# cpu.net
KiCad netlist of a schematic drawn in Altium Designer
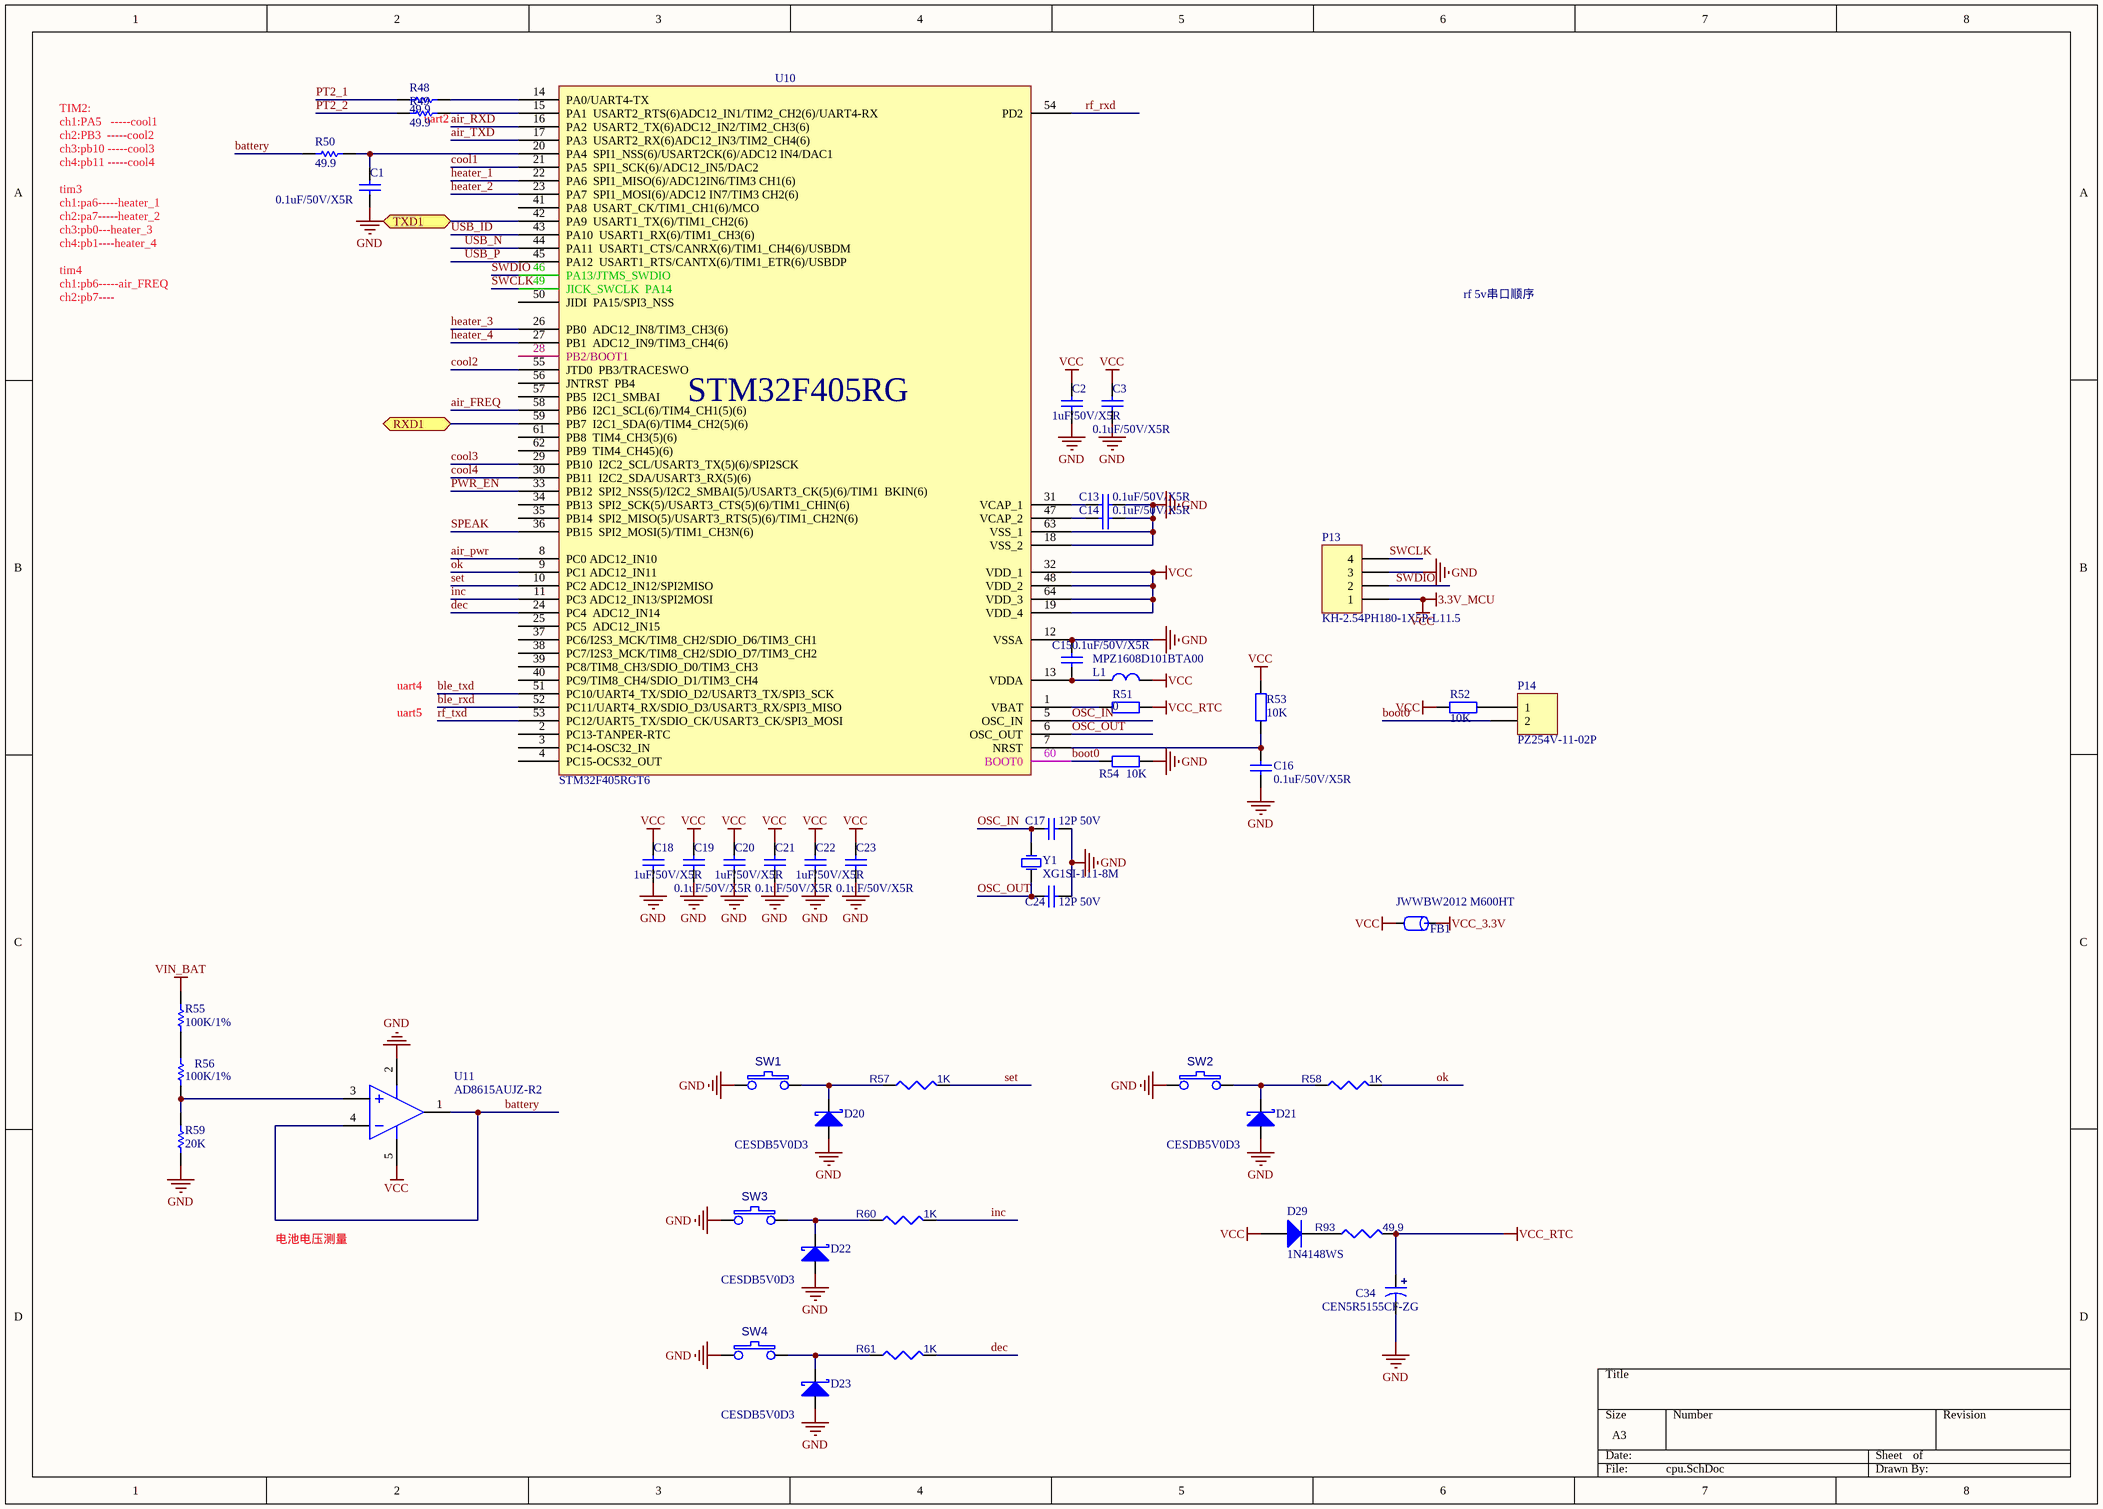
[diagram p0: cpu.SchDoc]

(export (version "E")
  (design (tool "Eeschema 10.0.6"))
  (components
    (comp (ref "C1")
      (value "0.1uF/50V/X5R")
      (footprint "0603C")
      (description "贴片电容 20%")
      (libsource (lib "XiaoyI") (part "CAP4"))
    )
    (comp (ref "C2")
      (value "1uF/50V/X5R")
      (footprint "0603C")
      (description "贴片电容 20%")
      (libsource (lib "XiaoyI") (part "CAP4"))
    )
    (comp (ref "C3")
      (value "0.1uF/50V/X5R")
      (footprint "0603C")
      (description "贴片电容 20%")
      (libsource (lib "XiaoyI") (part "CAP4"))
    )
    (comp (ref "C13")
      (value "0.1uF/50V/X5R")
      (footprint "0603C")
      (description "贴片电容 20%")
      (libsource (lib "XiaoyI") (part "CAP4"))
    )
    (comp (ref "C14")
      (value "0.1uF/50V/X5R")
      (footprint "0603C")
      (description "贴片电容 20%")
      (libsource (lib "XiaoyI") (part "CAP4"))
    )
    (comp (ref "C15")
      (value "0.1uF/50V/X5R")
      (footprint "0603C")
      (description "贴片电容 20%")
      (libsource (lib "XiaoyI") (part "CAP4"))
    )
    (comp (ref "C16")
      (value "0.1uF/50V/X5R")
      (footprint "0603C")
      (description "贴片电容 20%")
      (libsource (lib "XiaoyI") (part "CAP4"))
    )
    (comp (ref "C17")
      (value "12P 50V")
      (footprint "0603C")
      (description "贴片电容 20%")
      (libsource (lib "XiaoyI") (part "CAP4"))
    )
    (comp (ref "C18")
      (value "1uF/50V/X5R")
      (footprint "0603C")
      (description "贴片电容 20%")
      (libsource (lib "XiaoyI") (part "CAP4"))
    )
    (comp (ref "C19")
      (value "0.1uF/50V/X5R")
      (footprint "0603C")
      (description "贴片电容 20%")
      (libsource (lib "XiaoyI") (part "CAP4"))
    )
    (comp (ref "C20")
      (value "1uF/50V/X5R")
      (footprint "0603C")
      (description "贴片电容 20%")
      (libsource (lib "XiaoyI") (part "CAP4"))
    )
    (comp (ref "C21")
      (value "0.1uF/50V/X5R")
      (footprint "0603C")
      (description "贴片电容 20%")
      (libsource (lib "XiaoyI") (part "CAP4"))
    )
    (comp (ref "C22")
      (value "1uF/50V/X5R")
      (footprint "0603C")
      (description "贴片电容 20%")
      (libsource (lib "XiaoyI") (part "CAP4"))
    )
    (comp (ref "C23")
      (value "0.1uF/50V/X5R")
      (footprint "0603C")
      (description "贴片电容 20%")
      (libsource (lib "XiaoyI") (part "CAP4"))
    )
    (comp (ref "C24")
      (value "12P 50V")
      (footprint "0603C")
      (description "贴片电容 20%")
      (libsource (lib "XiaoyI") (part "CAP4"))
    )
    (comp (ref "C34")
      (value "CEN5R5155CF-ZG")
      (footprint "CAP-TH_BD21.0-P5.00-D0.8_CENXXX-CF")
      (description "电解电容")
      (libsource (lib "XiaoyI") (part "CAP2"))
    )
    (comp (ref "D20")
      (value "CESDB5V0D3")
      (footprint "SOD323")
      (description "Schottky Diode")
      (libsource (lib "*") (part "DIODE S"))
    )
    (comp (ref "D21")
      (value "CESDB5V0D3")
      (footprint "SOD323")
      (description "Schottky Diode")
      (libsource (lib "*") (part "DIODE S"))
    )
    (comp (ref "D22")
      (value "CESDB5V0D3")
      (footprint "SOD323")
      (description "Schottky Diode")
      (libsource (lib "*") (part "DIODE S"))
    )
    (comp (ref "D23")
      (value "CESDB5V0D3")
      (footprint "SOD323")
      (description "Schottky Diode")
      (libsource (lib "*") (part "DIODE S"))
    )
    (comp (ref "D29") (value "1N4148WS") (footprint "SOD323") (libsource (lib "Sch_library") (part "DIODE")))
    (comp (ref "FB1")
      (value "JWWBW2012 M600HT")
      (footprint "0805CZ")
      (libsource (lib "Schlib_20110825") (part "FB"))
    )
    (comp (ref "L1")
      (value "MPZ1608D101BTA00")
      (footprint "0603R")
      (description "磁珠电感 100R 100MHz")
      (libsource (lib "XiaoyI") (part "CIZHU1"))
    )
    (comp (ref "P13")
      (value "KH-2.54PH180-1X5P-L11.5")
      (footprint "HDR1X4")
      (description "Header, 4-Pin")
      (fields (field (name "PUBLISHER") "Altium Limited"))
      (libsource (lib "Miscellaneous Connectors") (part "Header 4"))
    )
    (comp (ref "P14")
      (value "PZ254V-11-02P")
      (footprint "HDR1X2")
      (description "Header, 2-Pin")
      (fields (field (name "PUBLISHER") "Altium Limited"))
      (libsource (lib "Miscellaneous Connectors") (part "Header 2"))
    )
    (comp (ref "R48")
      (value "49.9")
      (footprint "0603R")
      (description "Resistor")
      (fields (field (name "PUBLISHER") "Altium Limited"))
      (libsource (lib "Miscellaneous Devices") (part "Res1"))
    )
    (comp (ref "R49")
      (value "49.9")
      (footprint "0603R")
      (description "Resistor")
      (fields (field (name "PUBLISHER") "Altium Limited"))
      (libsource (lib "Miscellaneous Devices") (part "Res1"))
    )
    (comp (ref "R50")
      (value "49.9")
      (footprint "0603R")
      (description "Resistor")
      (fields (field (name "PUBLISHER") "Altium Limited"))
      (libsource (lib "Miscellaneous Devices") (part "Res1"))
    )
    (comp (ref "R51")
      (value "0")
      (footprint "0603R")
      (description "贴片电阻 5%")
      (libsource (lib "XiaoyI") (part "RES2"))
    )
    (comp (ref "R52")
      (value "10K")
      (footprint "0603R")
      (description "贴片电阻 5%")
      (libsource (lib "XiaoyI") (part "RES2"))
    )
    (comp (ref "R53")
      (value "10K")
      (footprint "0603R")
      (description "贴片电阻 5%")
      (libsource (lib "") (part "RES2_1"))
    )
    (comp (ref "R54")
      (value "10K")
      (footprint "0603R")
      (description "贴片电阻 5%")
      (libsource (lib "") (part "RES2_2"))
    )
    (comp (ref "R55")
      (value "100K/1%")
      (footprint "0603R")
      (description "Resistor")
      (fields (field (name "PUBLISHER") "Altium Limited"))
      (libsource (lib "Miscellaneous Devices") (part "Res1"))
    )
    (comp (ref "R56")
      (value "100K/1%")
      (footprint "0603R")
      (description "Resistor")
      (fields (field (name "PUBLISHER") "Altium Limited"))
      (libsource (lib "Miscellaneous Devices") (part "Res1"))
    )
    (comp (ref "R57")
      (value "1K")
      (footprint "0603R")
      (fields (field (name "Comment") "1k/1%"))
      (libsource (lib "*") (part "RESISTOR_0"))
    )
    (comp (ref "R58")
      (value "1K")
      (footprint "0603R")
      (fields (field (name "Comment") "1k/1%"))
      (libsource (lib "*") (part "RESISTOR_0"))
    )
    (comp (ref "R59")
      (value "20K")
      (footprint "0603R")
      (description "Resistor")
      (fields (field (name "PUBLISHER") "Altium Limited"))
      (libsource (lib "Miscellaneous Devices") (part "Res1"))
    )
    (comp (ref "R60")
      (value "1K")
      (footprint "0603R")
      (fields (field (name "Comment") "1k/1%"))
      (libsource (lib "*") (part "RESISTOR_0"))
    )
    (comp (ref "R61")
      (value "1K")
      (footprint "0603R")
      (fields (field (name "Comment") "1k/1%"))
      (libsource (lib "*") (part "RESISTOR_0"))
    )
    (comp (ref "R93")
      (value "49.9")
      (footprint "0603R")
      (fields (field (name "Comment") "1k/1%"))
      (libsource (lib "*") (part "RESISTOR_0"))
    )
    (comp (ref "SW1")
      (value "TS-1088-AR02016")
      (footprint "SW-SMD_L3.9-W3.0-P4.45")
      (libsource (lib "*") (part "SW PUSHBUTTON"))
    )
    (comp (ref "SW2")
      (value "TS-1088-AR02016")
      (footprint "SW-SMD_L3.9-W3.0-P4.45")
      (libsource (lib "*") (part "SW PUSHBUTTON"))
    )
    (comp (ref "SW3")
      (value "TS-1088-AR02016")
      (footprint "SW-SMD_L3.9-W3.0-P4.45")
      (libsource (lib "*") (part "SW PUSHBUTTON"))
    )
    (comp (ref "SW4")
      (value "TS-1088-AR02016")
      (footprint "SW-SMD_L3.9-W3.0-P4.45")
      (libsource (lib "*") (part "SW PUSHBUTTON"))
    )
    (comp (ref "U10")
      (value "STM32F405RGT6")
      (footprint "LQFP-64")
      (description "MCU")
      (libsource (lib "XiaoyI") (part "STM32F405RG"))
    )
    (comp (ref "U11")
      (value "AD8615AUJZ-R2")
      (footprint "sot-23-5")
      (libsource (lib "Schlib1") (part "AD8615"))
    )
    (comp (ref "Y1")
      (value "XG1SI-111-8M")
      (footprint "CRAY_5032")
      (description "晶振")
      (libsource (lib "XiaoyI") (part "XTAL"))
    )
  )
  (nets
    (net (code "1") (name "/OSC_IN") (class "Default")
      (node (ref "C17") (pin "2") (pinfunction "2_2") (pintype "passive"))
      (node (ref "U10") (pin "5") (pinfunction "OSC_IN_5") (pintype "passive"))
      (node (ref "Y1") (pin "2") (pinfunction "OSC2_2") (pintype "passive"))
    )
    (net (code "2") (name "/OSC_OUT") (class "Default")
      (node (ref "C24") (pin "2") (pinfunction "2_2") (pintype "passive"))
      (node (ref "U10") (pin "6") (pinfunction "OSC_OUT_6") (pintype "passive"))
      (node (ref "Y1") (pin "1") (pinfunction "OSC1_1") (pintype "passive"))
    )
    (net (code "3") (name "/PT2_1") (class "Default")
      (node (ref "R48") (pin "1") (pinfunction "1_1") (pintype "passive"))
    )
    (net (code "4") (name "/PT2_2") (class "Default")
      (node (ref "R49") (pin "1") (pinfunction "1_1") (pintype "passive"))
    )
    (net (code "5") (name "/PWR_EN") (class "Default")
      (node (ref "U10") (pin "33") (pinfunction "PB12__SPI2_NSS(5)/I2C2_SMBAI(5)/USART3_CK(5)(6)/TIM1__BKIN(6)_33") (pintype "passive"))
    )
    (net (code "6") (name "/RXD1") (class "Default")
      (node (ref "U10") (pin "59") (pinfunction "PB7__I2C1_SDA(6)/TIM4_CH2(5)(6)_59") (pintype "passive"))
    )
    (net (code "7") (name "/SPEAK") (class "Default")
      (node (ref "U10") (pin "36") (pinfunction "PB15__SPI2_MOSI(5)/TIM1_CH3N(6)_36") (pintype "passive"))
    )
    (net (code "8") (name "/SWCLK") (class "Default")
      (node (ref "P13") (pin "4") (pinfunction "4_4") (pintype "passive"))
      (node (ref "U10") (pin "49") (pinfunction "JICK_SWCLK__PA14_49") (pintype "passive"))
    )
    (net (code "9") (name "/SWDIO") (class "Default")
      (node (ref "P13") (pin "2") (pinfunction "2_2") (pintype "passive"))
      (node (ref "U10") (pin "46") (pinfunction "PA13/JTMS_SWDIO_46") (pintype "passive"))
    )
    (net (code "10") (name "/TXD1") (class "Default")
      (node (ref "U10") (pin "42") (pinfunction "PA9__USART1_TX(6)/TIM1_CH2(6)_42") (pintype "passive"))
    )
    (net (code "11") (name "/USB_ID") (class "Default")
      (node (ref "U10") (pin "43") (pinfunction "PA10__USART1_RX(6)/TIM1_CH3(6)_43") (pintype "passive"))
    )
    (net (code "12") (name "/USB_N") (class "Default")
      (node (ref "U10") (pin "44") (pinfunction "PA11__USART1_CTS/CANRX(6)/TIM1_CH4(6)/USBDM_44") (pintype "passive"))
    )
    (net (code "13") (name "/USB_P") (class "Default")
      (node (ref "U10") (pin "45") (pinfunction "PA12__USART1_RTS/CANTX(6)/TIM1_ETR(6)/USBDP_45") (pintype "passive"))
    )
    (net (code "14") (name "/air_FREQ") (class "Default")
      (node (ref "U10") (pin "58") (pinfunction "PB6__I2C1_SCL(6)/TIM4_CH1(5)(6)_58") (pintype "passive"))
    )
    (net (code "15") (name "/air_RXD") (class "Default")
      (node (ref "U10") (pin "16") (pinfunction "PA2__USART2_TX(6)ADC12_IN2/TIM2_CH3(6)_16") (pintype "passive"))
    )
    (net (code "16") (name "/air_TXD") (class "Default")
      (node (ref "U10") (pin "17") (pinfunction "PA3__USART2_RX(6)ADC12_IN3/TIM2_CH4(6)_17") (pintype "passive"))
    )
    (net (code "17") (name "/air_pwr") (class "Default")
      (node (ref "U10") (pin "8") (pinfunction "PC0_ADC12_IN10_8") (pintype "passive"))
    )
    (net (code "18") (name "/battery") (class "Default")
      (node (ref "R50") (pin "1") (pinfunction "1_1") (pintype "passive"))
      (node (ref "U11") (pin "1") (pinfunction "OS_NUL_1") (pintype "passive"))
      (node (ref "U11") (pin "4") (pinfunction "V-_4") (pintype "power_in"))
    )
    (net (code "19") (name "/ble_rxd") (class "Default")
      (node (ref "U10") (pin "52") (pinfunction "PC11/UART4_RX/SDIO_D3/USART3_RX/SPI3_MISO_52") (pintype "passive"))
    )
    (net (code "20") (name "/ble_txd") (class "Default")
      (node (ref "U10") (pin "51") (pinfunction "PC10/UART4_TX/SDIO_D2/USART3_TX/SPI3_SCK_51") (pintype "passive"))
    )
    (net (code "21") (name "/boot0") (class "Default")
      (node (ref "P14") (pin "2") (pinfunction "2_2") (pintype "passive"))
      (node (ref "R54") (pin "1") (pinfunction "1_1") (pintype "passive"))
      (node (ref "U10") (pin "60") (pinfunction "BOOT0_60") (pintype "passive"))
    )
    (net (code "22") (name "/cool1") (class "Default")
      (node (ref "U10") (pin "21") (pinfunction "PA5__SPI1_SCK(6)/ADC12_IN5/DAC2_21") (pintype "passive"))
    )
    (net (code "23") (name "/cool2") (class "Default")
      (node (ref "U10") (pin "55") (pinfunction "JTD0__PB3/TRACESWO_55") (pintype "passive"))
    )
    (net (code "24") (name "/cool3") (class "Default")
      (node (ref "U10") (pin "29") (pinfunction "PB10__I2C2_SCL/USART3_TX(5)(6)/SPI2SCK_29") (pintype "passive"))
    )
    (net (code "25") (name "/cool4") (class "Default")
      (node (ref "U10") (pin "30") (pinfunction "PB11__I2C2_SDA/USART3_RX(5)(6)_30") (pintype "passive"))
    )
    (net (code "26") (name "/dec") (class "Default")
      (node (ref "R61") (pin "2") (pinfunction "2_2") (pintype "passive"))
      (node (ref "U10") (pin "24") (pinfunction "PC4__ADC12_IN14_24") (pintype "passive"))
    )
    (net (code "27") (name "/heater_1") (class "Default")
      (node (ref "U10") (pin "22") (pinfunction "PA6__SPI1_MISO(6)/ADC12IN6/TIM3_CH1(6)_22") (pintype "passive"))
    )
    (net (code "28") (name "/heater_2") (class "Default")
      (node (ref "U10") (pin "23") (pinfunction "PA7__SPI1_MOSI(6)/ADC12_IN7/TIM3_CH2(6)_23") (pintype "passive"))
    )
    (net (code "29") (name "/heater_3") (class "Default")
      (node (ref "U10") (pin "26") (pinfunction "PB0__ADC12_IN8/TIM3_CH3(6)_26") (pintype "passive"))
    )
    (net (code "30") (name "/heater_4") (class "Default")
      (node (ref "U10") (pin "27") (pinfunction "PB1__ADC12_IN9/TIM3_CH4(6)_27") (pintype "passive"))
    )
    (net (code "31") (name "/inc") (class "Default")
      (node (ref "R60") (pin "2") (pinfunction "2_2") (pintype "passive"))
      (node (ref "U10") (pin "11") (pinfunction "PC3_ADC12_IN13/SPI2MOSI_11") (pintype "passive"))
    )
    (net (code "32") (name "/ok") (class "Default")
      (node (ref "R58") (pin "2") (pinfunction "2_2") (pintype "passive"))
      (node (ref "U10") (pin "9") (pinfunction "PC1_ADC12_IN11_9") (pintype "passive"))
    )
    (net (code "33") (name "/rf_rxd") (class "Default")
      (node (ref "U10") (pin "54") (pinfunction "PD2_54") (pintype "passive"))
    )
    (net (code "34") (name "/rf_txd") (class "Default")
      (node (ref "U10") (pin "53") (pinfunction "PC12/UART5_TX/SDIO_CK/USART3_CK/SPI3_MOSI_53") (pintype "passive"))
    )
    (net (code "35") (name "/set") (class "Default")
      (node (ref "R57") (pin "2") (pinfunction "2_2") (pintype "passive"))
      (node (ref "U10") (pin "10") (pinfunction "PC2_ADC12_IN12/SPI2MISO_10") (pintype "passive"))
    )
    (net (code "36") (name "3.3V_MCU") (class "Default")
      (node (ref "C18") (pin "2") (pinfunction "2_2") (pintype "passive"))
      (node (ref "C19") (pin "2") (pinfunction "2_2") (pintype "passive"))
      (node (ref "C2") (pin "2") (pinfunction "2_2") (pintype "passive"))
      (node (ref "C20") (pin "2") (pinfunction "2_2") (pintype "passive"))
      (node (ref "C21") (pin "2") (pinfunction "2_2") (pintype "passive"))
      (node (ref "C22") (pin "2") (pinfunction "2_2") (pintype "passive"))
      (node (ref "C23") (pin "2") (pinfunction "2_2") (pintype "passive"))
      (node (ref "C3") (pin "2") (pinfunction "2_2") (pintype "passive"))
      (node (ref "D29") (pin "1") (pinfunction "A_1") (pintype "passive"))
      (node (ref "FB1") (pin "2") (pintype "passive"))
      (node (ref "L1") (pin "2") (pinfunction "2_2") (pintype "passive"))
      (node (ref "P13") (pin "1") (pinfunction "1_1") (pintype "passive"))
      (node (ref "R52") (pin "2") (pinfunction "2_2") (pintype "passive"))
      (node (ref "R53") (pin "1") (pinfunction "1_1") (pintype "passive"))
      (node (ref "U10") (pin "19") (pinfunction "VDD_4_19") (pintype "passive"))
      (node (ref "U10") (pin "32") (pinfunction "VDD_1_32") (pintype "passive"))
      (node (ref "U10") (pin "48") (pinfunction "VDD_2_48") (pintype "passive"))
      (node (ref "U10") (pin "64") (pinfunction "VDD_3_64") (pintype "passive"))
      (node (ref "U11") (pin "5") (pinfunction "VCC_5") (pintype "passive"))
    )
    (net (code "37") (name "GND") (class "Default")
      (node (ref "C1") (pin "1") (pinfunction "1_1") (pintype "passive"))
      (node (ref "C13") (pin "1") (pinfunction "1_1") (pintype "passive"))
      (node (ref "C14") (pin "1") (pinfunction "1_1") (pintype "passive"))
      (node (ref "C15") (pin "1") (pinfunction "1_1") (pintype "passive"))
      (node (ref "C16") (pin "1") (pinfunction "1_1") (pintype "passive"))
      (node (ref "C17") (pin "1") (pinfunction "1_1") (pintype "passive"))
      (node (ref "C18") (pin "1") (pinfunction "1_1") (pintype "passive"))
      (node (ref "C19") (pin "1") (pinfunction "1_1") (pintype "passive"))
      (node (ref "C2") (pin "1") (pinfunction "1_1") (pintype "passive"))
      (node (ref "C20") (pin "1") (pinfunction "1_1") (pintype "passive"))
      (node (ref "C21") (pin "1") (pinfunction "1_1") (pintype "passive"))
      (node (ref "C22") (pin "1") (pinfunction "1_1") (pintype "passive"))
      (node (ref "C23") (pin "1") (pinfunction "1_1") (pintype "passive"))
      (node (ref "C24") (pin "1") (pinfunction "1_1") (pintype "passive"))
      (node (ref "C3") (pin "1") (pinfunction "1_1") (pintype "passive"))
      (node (ref "C34") (pin "2") (pinfunction "2_2") (pintype "passive"))
      (node (ref "D20") (pin "1") (pinfunction "A_1") (pintype "passive"))
      (node (ref "D21") (pin "1") (pinfunction "A_1") (pintype "passive"))
      (node (ref "D22") (pin "1") (pinfunction "A_1") (pintype "passive"))
      (node (ref "D23") (pin "1") (pinfunction "A_1") (pintype "passive"))
      (node (ref "P13") (pin "3") (pinfunction "3_3") (pintype "passive"))
      (node (ref "R54") (pin "2") (pinfunction "2_2") (pintype "passive"))
      (node (ref "R59") (pin "2") (pinfunction "2_2") (pintype "passive"))
      (node (ref "SW1") (pin "1") (pinfunction "1_1") (pintype "passive"))
      (node (ref "SW2") (pin "1") (pinfunction "1_1") (pintype "passive"))
      (node (ref "SW3") (pin "1") (pinfunction "1_1") (pintype "passive"))
      (node (ref "SW4") (pin "1") (pinfunction "1_1") (pintype "passive"))
      (node (ref "U10") (pin "12") (pinfunction "VSSA_12") (pintype "passive"))
      (node (ref "U10") (pin "18") (pinfunction "VSS_2_18") (pintype "passive"))
      (node (ref "U10") (pin "63") (pinfunction "VSS_1_63") (pintype "passive"))
      (node (ref "U11") (pin "2") (pinfunction "G_2") (pintype "power_in"))
    )
    (net (code "38") (name "Net-(D20-K)") (class "Default")
      (node (ref "D20") (pin "2") (pinfunction "K_2") (pintype "passive"))
      (node (ref "R57") (pin "1") (pinfunction "1_1") (pintype "passive"))
      (node (ref "SW1") (pin "2") (pinfunction "2_2") (pintype "passive"))
    )
    (net (code "39") (name "Net-(D21-K)") (class "Default")
      (node (ref "D21") (pin "2") (pinfunction "K_2") (pintype "passive"))
      (node (ref "R58") (pin "1") (pinfunction "1_1") (pintype "passive"))
      (node (ref "SW2") (pin "2") (pinfunction "2_2") (pintype "passive"))
    )
    (net (code "40") (name "Net-(D22-K)") (class "Default")
      (node (ref "D22") (pin "2") (pinfunction "K_2") (pintype "passive"))
      (node (ref "R60") (pin "1") (pinfunction "1_1") (pintype "passive"))
      (node (ref "SW3") (pin "2") (pinfunction "2_2") (pintype "passive"))
    )
    (net (code "41") (name "Net-(D23-K)") (class "Default")
      (node (ref "D23") (pin "2") (pinfunction "K_2") (pintype "passive"))
      (node (ref "R61") (pin "1") (pinfunction "1_1") (pintype "passive"))
      (node (ref "SW4") (pin "2") (pinfunction "2_2") (pintype "passive"))
    )
    (net (code "42") (name "Net-(D29-K)") (class "Default")
      (node (ref "D29") (pin "2") (pinfunction "K_2") (pintype "passive"))
      (node (ref "R93") (pin "1") (pinfunction "1_1") (pintype "passive"))
    )
    (net (code "43") (name "Net-(P14-Pad1)") (class "Default")
      (node (ref "P14") (pin "1") (pinfunction "1_1") (pintype "passive"))
      (node (ref "R52") (pin "1") (pinfunction "1_1") (pintype "passive"))
    )
    (net (code "44") (name "Net-(R55-Pad2)") (class "Default")
      (node (ref "R55") (pin "2") (pinfunction "2_2") (pintype "passive"))
      (node (ref "R56") (pin "1") (pinfunction "1_1") (pintype "passive"))
    )
    (net (code "45") (name "Net-(U10-NRST)") (class "Default")
      (node (ref "C16") (pin "2") (pinfunction "2_2") (pintype "passive"))
      (node (ref "R53") (pin "2") (pinfunction "2_2") (pintype "passive"))
      (node (ref "U10") (pin "7") (pinfunction "NRST_7") (pintype "passive"))
    )
    (net (code "46") (name "Net-(U10-PA0{slash}UART4-TX)") (class "Default")
      (node (ref "R48") (pin "2") (pinfunction "2_2") (pintype "passive"))
      (node (ref "U10") (pin "14") (pinfunction "PA0/UART4-TX_14") (pintype "passive"))
    )
    (net (code "47") (name "Net-(U10-PA1__USART2_RTS(6)ADC12_IN1{slash}TIM2_CH2(6){slash}UART4-RX)") (class "Default")
      (node (ref "R49") (pin "2") (pinfunction "2_2") (pintype "passive"))
      (node (ref "U10") (pin "15") (pinfunction "PA1__USART2_RTS(6)ADC12_IN1/TIM2_CH2(6)/UART4-RX_15") (pintype "passive"))
    )
    (net (code "48") (name "Net-(U10-PA4__SPI1_NSS(6){slash}USART2CK(6){slash}ADC12_IN4{slash}DAC1)") (class "Default")
      (node (ref "C1") (pin "2") (pinfunction "2_2") (pintype "passive"))
      (node (ref "R50") (pin "2") (pinfunction "2_2") (pintype "passive"))
      (node (ref "U10") (pin "20") (pinfunction "PA4__SPI1_NSS(6)/USART2CK(6)/ADC12_IN4/DAC1_20") (pintype "passive"))
    )
    (net (code "49") (name "Net-(U10-VBAT)") (class "Default")
      (node (ref "R51") (pin "2") (pinfunction "2_2") (pintype "passive"))
      (node (ref "U10") (pin "1") (pinfunction "VBAT_1") (pintype "passive"))
    )
    (net (code "50") (name "Net-(U10-VCAP_1)") (class "Default")
      (node (ref "C13") (pin "2") (pinfunction "2_2") (pintype "passive"))
      (node (ref "U10") (pin "31") (pinfunction "VCAP_1_31") (pintype "passive"))
    )
    (net (code "51") (name "Net-(U10-VCAP_2)") (class "Default")
      (node (ref "C14") (pin "2") (pinfunction "2_2") (pintype "passive"))
      (node (ref "U10") (pin "47") (pinfunction "VCAP_2_47") (pintype "passive"))
    )
    (net (code "52") (name "Net-(U10-VDDA)") (class "Default")
      (node (ref "C15") (pin "2") (pinfunction "2_2") (pintype "passive"))
      (node (ref "L1") (pin "1") (pinfunction "1_1") (pintype "passive"))
      (node (ref "U10") (pin "13") (pinfunction "VDDA_13") (pintype "passive"))
    )
    (net (code "53") (name "Net-(U11-V+)") (class "Default")
      (node (ref "R56") (pin "2") (pinfunction "2_2") (pintype "passive"))
      (node (ref "R59") (pin "1") (pinfunction "1_1") (pintype "passive"))
      (node (ref "U11") (pin "3") (pinfunction "V+_3") (pintype "power_in"))
    )
    (net (code "54") (name "VCC_3.3V") (class "Default") (node (ref "FB1") (pin "1") (pintype "passive")))
    (net (code "55") (name "VCC_RTC") (class "Default")
      (node (ref "C34") (pin "1") (pinfunction "1_1") (pintype "passive"))
      (node (ref "R51") (pin "1") (pinfunction "1_1") (pintype "passive"))
      (node (ref "R93") (pin "2") (pinfunction "2_2") (pintype "passive"))
    )
    (net (code "56") (name "VIN_BAT") (class "Default")
      (node (ref "R55") (pin "1") (pinfunction "1_1") (pintype "passive"))
    )
    (net (code "57") (name "unconnected-(U10-JIDI__PA15{slash}SPI3_NSS-Pad50)") (class "Default")
      (node (ref "U10") (pin "50") (pinfunction "JIDI__PA15/SPI3_NSS_50") (pintype "passive"))
    )
    (net (code "58") (name "unconnected-(U10-JNTRST__PB4-Pad56)") (class "Default")
      (node (ref "U10") (pin "56") (pinfunction "JNTRST__PB4_56") (pintype "passive"))
    )
    (net (code "59") (name "unconnected-(U10-PA8__USART_CK{slash}TIM1_CH1(6){slash}MCO-Pad41)") (class "Default")
      (node (ref "U10") (pin "41") (pinfunction "PA8__USART_CK/TIM1_CH1(6)/MCO_41") (pintype "passive"))
    )
    (net (code "60") (name "unconnected-(U10-PB2{slash}BOOT1-Pad28)") (class "Default")
      (node (ref "U10") (pin "28") (pinfunction "PB2/BOOT1_28") (pintype "passive"))
    )
    (net (code "61") (name "unconnected-(U10-PB5__I2C1_SMBAI-Pad57)") (class "Default")
      (node (ref "U10") (pin "57") (pinfunction "PB5__I2C1_SMBAI_57") (pintype "passive"))
    )
    (net (code "62") (name "unconnected-(U10-PB8__TIM4_CH3(5)(6)-Pad61)") (class "Default")
      (node (ref "U10") (pin "61") (pinfunction "PB8__TIM4_CH3(5)(6)_61") (pintype "passive"))
    )
    (net (code "63") (name "unconnected-(U10-PB9__TIM4_CH45)(6)-Pad62)") (class "Default")
      (node (ref "U10") (pin "62") (pinfunction "PB9__TIM4_CH45)(6)_62") (pintype "passive"))
    )
    (net (code "64") (name "unconnected-(U10-PB13__SPI2_SCK(5){slash}USART3_CTS(5)(6){slash}TIM1_CHIN(6)-Pad34)") (class "Default")
      (node (ref "U10") (pin "34") (pinfunction "PB13__SPI2_SCK(5)/USART3_CTS(5)(6)/TIM1_CHIN(6)_34") (pintype "passive"))
    )
    (net (code "65") (name "unconnected-(U10-PB14__SPI2_MISO(5){slash}USART3_RTS(5)(6){slash}TIM1_CH2N(6)-Pad35)") (class "Default")
      (node (ref "U10") (pin "35") (pinfunction "PB14__SPI2_MISO(5)/USART3_RTS(5)(6)/TIM1_CH2N(6)_35") (pintype "passive"))
    )
    (net (code "66") (name "unconnected-(U10-PC5__ADC12_IN15-Pad25)") (class "Default")
      (node (ref "U10") (pin "25") (pinfunction "PC5__ADC12_IN15_25") (pintype "passive"))
    )
    (net (code "67") (name "unconnected-(U10-PC6{slash}I2S3_MCK{slash}TIM8_CH2{slash}SDIO_D6{slash}TIM3_CH1-Pad37)") (class "Default")
      (node (ref "U10") (pin "37") (pinfunction "PC6/I2S3_MCK/TIM8_CH2/SDIO_D6/TIM3_CH1_37") (pintype "passive"))
    )
    (net (code "68") (name "unconnected-(U10-PC7{slash}I2S3_MCK{slash}TIM8_CH2{slash}SDIO_D7{slash}TIM3_CH2-Pad38)") (class "Default")
      (node (ref "U10") (pin "38") (pinfunction "PC7/I2S3_MCK/TIM8_CH2/SDIO_D7/TIM3_CH2_38") (pintype "passive"))
    )
    (net (code "69") (name "unconnected-(U10-PC8{slash}TIM8_CH3{slash}SDIO_D0{slash}TIM3_CH3-Pad39)") (class "Default")
      (node (ref "U10") (pin "39") (pinfunction "PC8/TIM8_CH3/SDIO_D0/TIM3_CH3_39") (pintype "passive"))
    )
    (net (code "70") (name "unconnected-(U10-PC9{slash}TIM8_CH4{slash}SDIO_D1{slash}TIM3_CH4-Pad40)") (class "Default")
      (node (ref "U10") (pin "40") (pinfunction "PC9/TIM8_CH4/SDIO_D1/TIM3_CH4_40") (pintype "passive"))
    )
    (net (code "71") (name "unconnected-(U10-PC13-TANPER-RTC-Pad2)") (class "Default")
      (node (ref "U10") (pin "2") (pinfunction "PC13-TANPER-RTC_2") (pintype "passive"))
    )
    (net (code "72") (name "unconnected-(U10-PC14-OSC32_IN-Pad3)") (class "Default")
      (node (ref "U10") (pin "3") (pinfunction "PC14-OSC32_IN_3") (pintype "passive"))
    )
    (net (code "73") (name "unconnected-(U10-PC15-OCS32_OUT-Pad4)") (class "Default")
      (node (ref "U10") (pin "4") (pinfunction "PC15-OCS32_OUT_4") (pintype "passive"))
    )
  )
)
